# rx.net
KiCad netlist of a schematic drawn in EAGLE
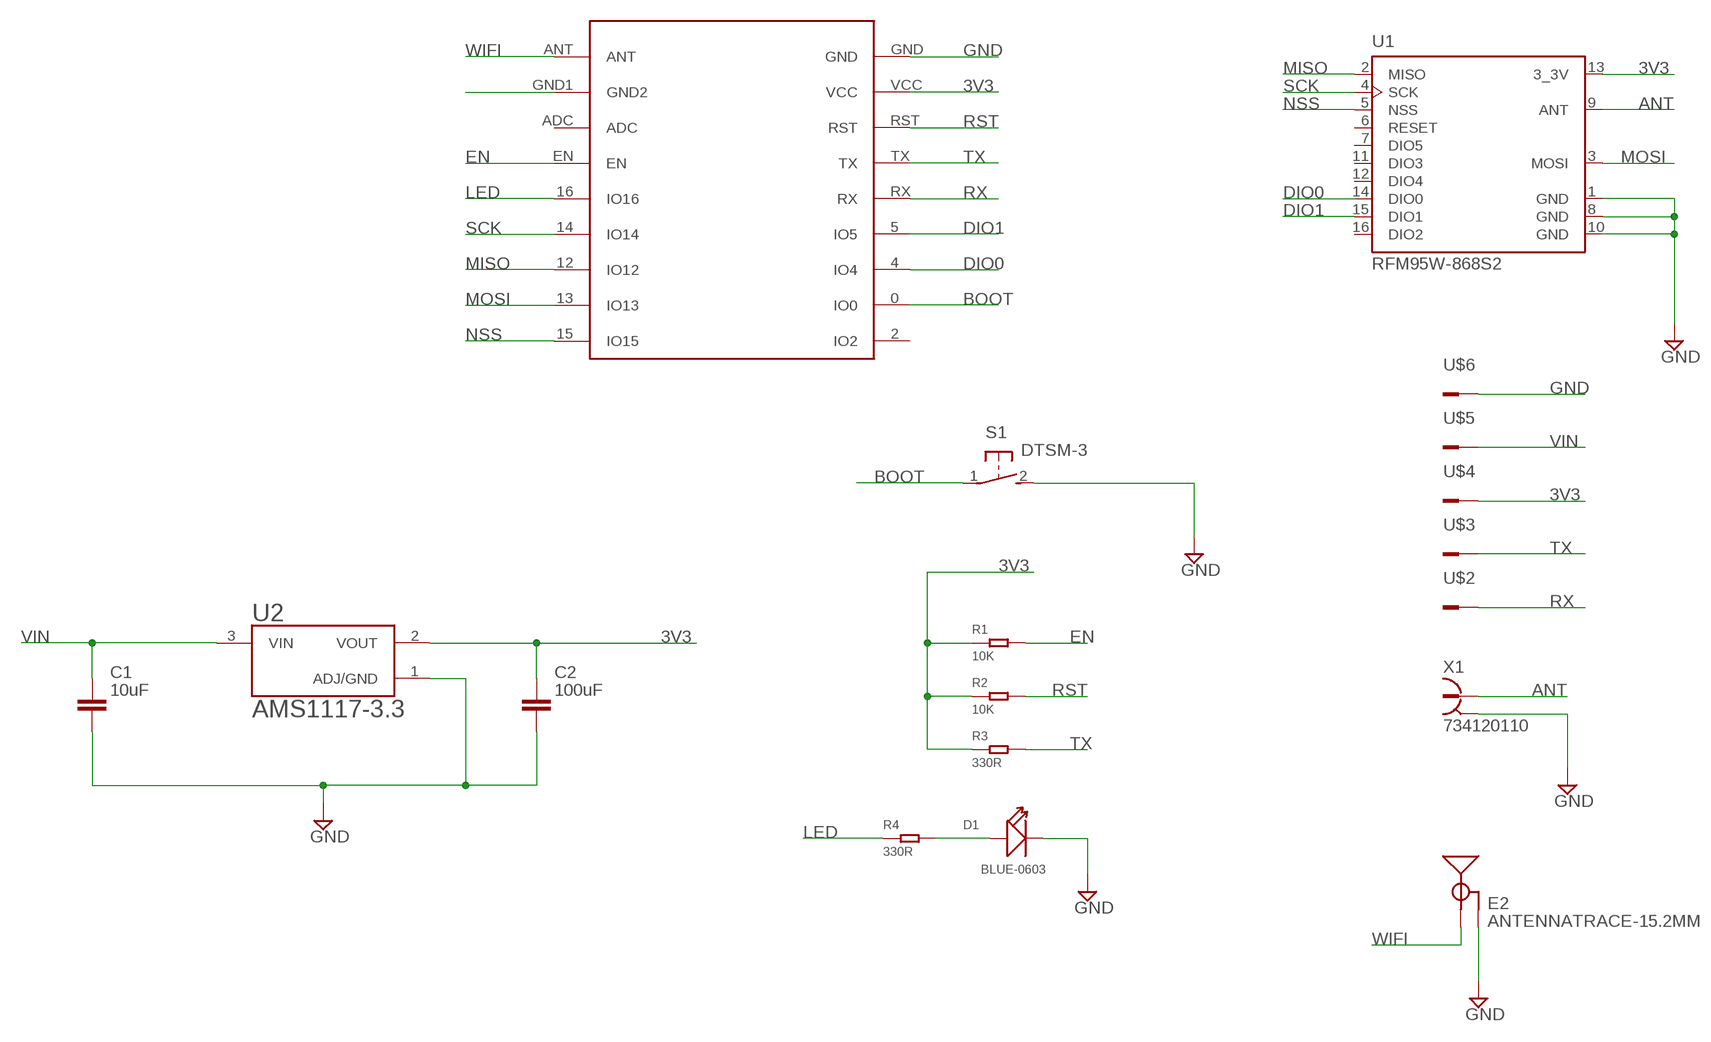
[diagram p0: schematic, sheet 1]

(export (version "E")
  (design (tool "Eeschema 10.0.6"))
  (components
    (comp (ref "C1")
      (value "10uF")
      (footprint "eagle-import:CAPM3528X210")
      (libsource (lib "eagle-import") (part "CTANTALUM-1411(3528-METRIC)_"))
    )
    (comp (ref "C2")
      (value "100uF")
      (footprint "eagle-import:CAPM3528X210")
      (libsource (lib "eagle-import") (part "CTANTALUM-1411(3528-METRIC)_"))
    )
    (comp (ref "D1")
      (value "BLUE-0603")
      (footprint "eagle-import:LED-0603")
      (fields (field (name "MPN") "19-217-BHC-ZL1M2RY-3T"))
      (libsource (lib "eagle-import") (part "SMD-LED-CLEAR-BLUE(0603)"))
    )
    (comp (ref "E2")
      (value "ANTENNATRACE-15.2MM")
      (footprint "eagle-import:TRACE_ANTENNA_2.4GHZ_15.2MM")
      (libsource (lib "eagle-import") (part "ANTENNATRACE-15.2MM"))
    )
    (comp (ref "R1")
      (value "10K")
      (footprint "eagle-import:R0805")
      (fields (field (name "MPN") "RC0805FR-0710KL"))
      (libsource (lib "eagle-import") (part "SMD-RES-10K-1%-1/8W(0805)"))
    )
    (comp (ref "R2")
      (value "10K")
      (footprint "eagle-import:R0805")
      (fields (field (name "MPN") "RC0805FR-0710KL"))
      (libsource (lib "eagle-import") (part "SMD-RES-10K-1%-1/8W(0805)"))
    )
    (comp (ref "R3")
      (value "330R")
      (footprint "eagle-import:R0805")
      (fields (field (name "MPN") "RC0805JR-071KL"))
      (libsource (lib "eagle-import") (part "SMD-RES-330R-5%-1/8W(0805)"))
    )
    (comp (ref "R4")
      (value "330R")
      (footprint "eagle-import:R0805")
      (fields (field (name "MPN") "RC0805JR-071KL"))
      (libsource (lib "eagle-import") (part "SMD-RES-330R-5%-1/8W(0805)"))
    )
    (comp (ref "S1")
      (value "DTSM-3")
      (footprint "eagle-import:DTSM-3")
      (libsource (lib "eagle-import") (part "DTSM-3"))
    )
    (comp (ref "U$1")
      (value "ESP-M2")
      (footprint "eagle-import:ESP-M2")
      (fields
        (field (name "MF") "Doctors of Intelligence & Technology Co., LTD")
        (field (name "MP") " ESP-M2 ")
      )
      (libsource (lib "eagle-import") (part "ESP-M2"))
    )
    (comp (ref "U$2")
      (value "CONN-1")
      (footprint "eagle-import:PAD1")
      (libsource (lib "eagle-import") (part "CONN-1"))
    )
    (comp (ref "U$3")
      (value "CONN-1")
      (footprint "eagle-import:PAD1")
      (libsource (lib "eagle-import") (part "CONN-1"))
    )
    (comp (ref "U$4")
      (value "CONN-1")
      (footprint "eagle-import:PAD1")
      (libsource (lib "eagle-import") (part "CONN-1"))
    )
    (comp (ref "U$5")
      (value "CONN-1")
      (footprint "eagle-import:PAD1")
      (libsource (lib "eagle-import") (part "CONN-1"))
    )
    (comp (ref "U$6")
      (value "CONN-1")
      (footprint "eagle-import:PAD1")
      (libsource (lib "eagle-import") (part "CONN-1"))
    )
    (comp (ref "U1")
      (value "RFM95W-868S2")
      (footprint "eagle-import:XCVR_RFM95W-868S2")
      (fields (field (name "MF") "RF"))
      (libsource (lib "eagle-import") (part "RFM95W-868S2"))
    )
    (comp (ref "U2")
      (value "AMS1117-3.3")
      (footprint "eagle-import:SOT229P700X180-4N")
      (fields (field (name "MF") "Advanced Monolithic Systems"))
      (libsource (lib "eagle-import") (part "AMS1117-3.3"))
    )
    (comp (ref "X1")
      (value "734120110")
      (footprint "eagle-import:734120110")
      (fields (field (name "MF") "Molex") (field (name "MP") "734-12-0110"))
      (libsource (lib "eagle-import") (part "734120110"))
    )
  )
  (nets
    (net (code "1") (name "/3V3") (class "Default")
      (node (ref "C2") (pin "1") (pinfunction "1_1") (pintype "passive"))
      (node (ref "R1") (pin "1") (pinfunction "1_1") (pintype "passive"))
      (node (ref "R2") (pin "1") (pinfunction "1_1") (pintype "passive"))
      (node (ref "R3") (pin "1") (pinfunction "1_1") (pintype "passive"))
      (node (ref "U$1") (pin "VCC") (pinfunction "VCC_VCC") (pintype "bidirectional"))
      (node (ref "U$4") (pin "P$1") (pinfunction "1_P$1") (pintype "passive"))
      (node (ref "U1") (pin "13") (pinfunction "3_3V_13") (pintype "power_in"))
      (node (ref "U2") (pin "2") (pinfunction "VOUT_2") (pintype "output"))
    )
    (net (code "2") (name "/ANT") (class "Default")
      (node (ref "U1") (pin "9") (pinfunction "ANT_9") (pintype "passive"))
      (node (ref "X1") (pin "1") (pinfunction "1_1") (pintype "passive"))
    )
    (net (code "3") (name "/BOOT") (class "Default")
      (node (ref "S1") (pin "1") (pinfunction "1_1") (pintype "passive"))
      (node (ref "U$1") (pin "0") (pinfunction "IO0_0") (pintype "bidirectional"))
    )
    (net (code "4") (name "/DIO0") (class "Default")
      (node (ref "U$1") (pin "4") (pinfunction "IO4_4") (pintype "bidirectional"))
      (node (ref "U1") (pin "14") (pinfunction "DIO0_14") (pintype "bidirectional"))
    )
    (net (code "5") (name "/DIO1") (class "Default")
      (node (ref "U$1") (pin "5") (pinfunction "IO5_5") (pintype "bidirectional"))
      (node (ref "U1") (pin "15") (pinfunction "DIO1_15") (pintype "bidirectional"))
    )
    (net (code "6") (name "/EN") (class "Default")
      (node (ref "R1") (pin "2") (pinfunction "2_2") (pintype "passive"))
      (node (ref "U$1") (pin "EN") (pinfunction "EN_EN") (pintype "bidirectional"))
    )
    (net (code "7") (name "/LED") (class "Default")
      (node (ref "R4") (pin "1") (pinfunction "1_1") (pintype "passive"))
      (node (ref "U$1") (pin "16") (pinfunction "IO16_16") (pintype "bidirectional"))
    )
    (net (code "8") (name "/MISO") (class "Default")
      (node (ref "U$1") (pin "12") (pinfunction "IO12_12") (pintype "bidirectional"))
      (node (ref "U1") (pin "2") (pinfunction "MISO_2") (pintype "input"))
    )
    (net (code "9") (name "/MOSI") (class "Default")
      (node (ref "U$1") (pin "13") (pinfunction "IO13_13") (pintype "bidirectional"))
      (node (ref "U1") (pin "3") (pinfunction "MOSI_3") (pintype "output"))
    )
    (net (code "10") (name "/NSS") (class "Default")
      (node (ref "U$1") (pin "15") (pinfunction "IO15_15") (pintype "bidirectional"))
      (node (ref "U1") (pin "5") (pinfunction "NSS_5") (pintype "input"))
    )
    (net (code "11") (name "/RST") (class "Default")
      (node (ref "R2") (pin "2") (pinfunction "2_2") (pintype "passive"))
      (node (ref "U$1") (pin "RST") (pinfunction "RST_RST") (pintype "bidirectional"))
    )
    (net (code "12") (name "/RX") (class "Default")
      (node (ref "U$1") (pin "RX") (pinfunction "RX_RX") (pintype "bidirectional"))
      (node (ref "U$2") (pin "P$1") (pinfunction "1_P$1") (pintype "passive"))
    )
    (net (code "13") (name "/SCK") (class "Default")
      (node (ref "U$1") (pin "14") (pinfunction "IO14_14") (pintype "bidirectional"))
      (node (ref "U1") (pin "4") (pinfunction "SCK_4") (pintype "input"))
    )
    (net (code "14") (name "/TX") (class "Default")
      (node (ref "R3") (pin "2") (pinfunction "2_2") (pintype "passive"))
      (node (ref "U$1") (pin "TX") (pinfunction "TX_TX") (pintype "bidirectional"))
      (node (ref "U$3") (pin "P$1") (pinfunction "1_P$1") (pintype "passive"))
    )
    (net (code "15") (name "/VIN") (class "Default")
      (node (ref "C1") (pin "1") (pinfunction "1_1") (pintype "passive"))
      (node (ref "U$5") (pin "P$1") (pinfunction "1_P$1") (pintype "passive"))
      (node (ref "U2") (pin "3") (pinfunction "VIN_3") (pintype "input"))
    )
    (net (code "16") (name "/WIFI") (class "Default")
      (node (ref "E2") (pin "ANT") (pinfunction "SIGNAL_ANT") (pintype "bidirectional"))
      (node (ref "U$1") (pin "ANT") (pinfunction "ANT_ANT") (pintype "bidirectional"))
    )
    (net (code "17") (name "GND") (class "Default")
      (node (ref "C1") (pin "2") (pinfunction "2_2") (pintype "passive"))
      (node (ref "C2") (pin "2") (pinfunction "2_2") (pintype "passive"))
      (node (ref "D1") (pin "-") (pinfunction "-_-") (pintype "passive"))
      (node (ref "E2") (pin "GND") (pinfunction "GND_GND") (pintype "bidirectional"))
      (node (ref "S1") (pin "2") (pinfunction "2_2") (pintype "passive"))
      (node (ref "U$1") (pin "GND") (pinfunction "GND_GND") (pintype "bidirectional"))
      (node (ref "U$1") (pin "GND1") (pinfunction "GND2_GND1") (pintype "bidirectional"))
      (node (ref "U$6") (pin "P$1") (pinfunction "1_P$1") (pintype "passive"))
      (node (ref "U1") (pin "1") (pinfunction "GND_1") (pintype "power_in"))
      (node (ref "U1") (pin "10") (pinfunction "GND_10") (pintype "power_in"))
      (node (ref "U1") (pin "8") (pinfunction "GND_8") (pintype "power_in"))
      (node (ref "U2") (pin "1") (pinfunction "ADJ/GND_1") (pintype "power_in"))
      (node (ref "X1") (pin "S@1") (pinfunction "2_S@1") (pintype "passive"))
      (node (ref "X1") (pin "S@2") (pinfunction "2_S@2") (pintype "passive"))
      (node (ref "X1") (pin "S@3") (pinfunction "2_S@3") (pintype "passive"))
    )
    (net (code "18") (name "Net-(D1-Pad+)") (class "Default")
      (node (ref "D1") (pin "+") (pinfunction "+_+") (pintype "passive"))
      (node (ref "R4") (pin "2") (pinfunction "2_2") (pintype "passive"))
    )
    (net (code "19") (name "unconnected-(U$1-IO2-Pad2)") (class "Default")
      (node (ref "U$1") (pin "2") (pinfunction "IO2_2") (pintype "bidirectional"))
    )
    (net (code "20") (name "unconnected-(U$1-PadADC)") (class "Default")
      (node (ref "U$1") (pin "ADC") (pinfunction "ADC_ADC") (pintype "bidirectional"))
    )
    (net (code "21") (name "unconnected-(U1-DIO2-Pad16)") (class "Default")
      (node (ref "U1") (pin "16") (pinfunction "DIO2_16") (pintype "bidirectional"))
    )
    (net (code "22") (name "unconnected-(U1-DIO3-Pad11)") (class "Default")
      (node (ref "U1") (pin "11") (pinfunction "DIO3_11") (pintype "bidirectional"))
    )
    (net (code "23") (name "unconnected-(U1-DIO4-Pad12)") (class "Default")
      (node (ref "U1") (pin "12") (pinfunction "DIO4_12") (pintype "bidirectional"))
    )
    (net (code "24") (name "unconnected-(U1-DIO5-Pad7)") (class "Default")
      (node (ref "U1") (pin "7") (pinfunction "DIO5_7") (pintype "bidirectional"))
    )
    (net (code "25") (name "unconnected-(U1-RESET-Pad6)") (class "Default")
      (node (ref "U1") (pin "6") (pinfunction "RESET_6") (pintype "bidirectional"))
    )
  )
)
